# Utility_Module.net
KiCad netlist of a schematic drawn in EAGLE
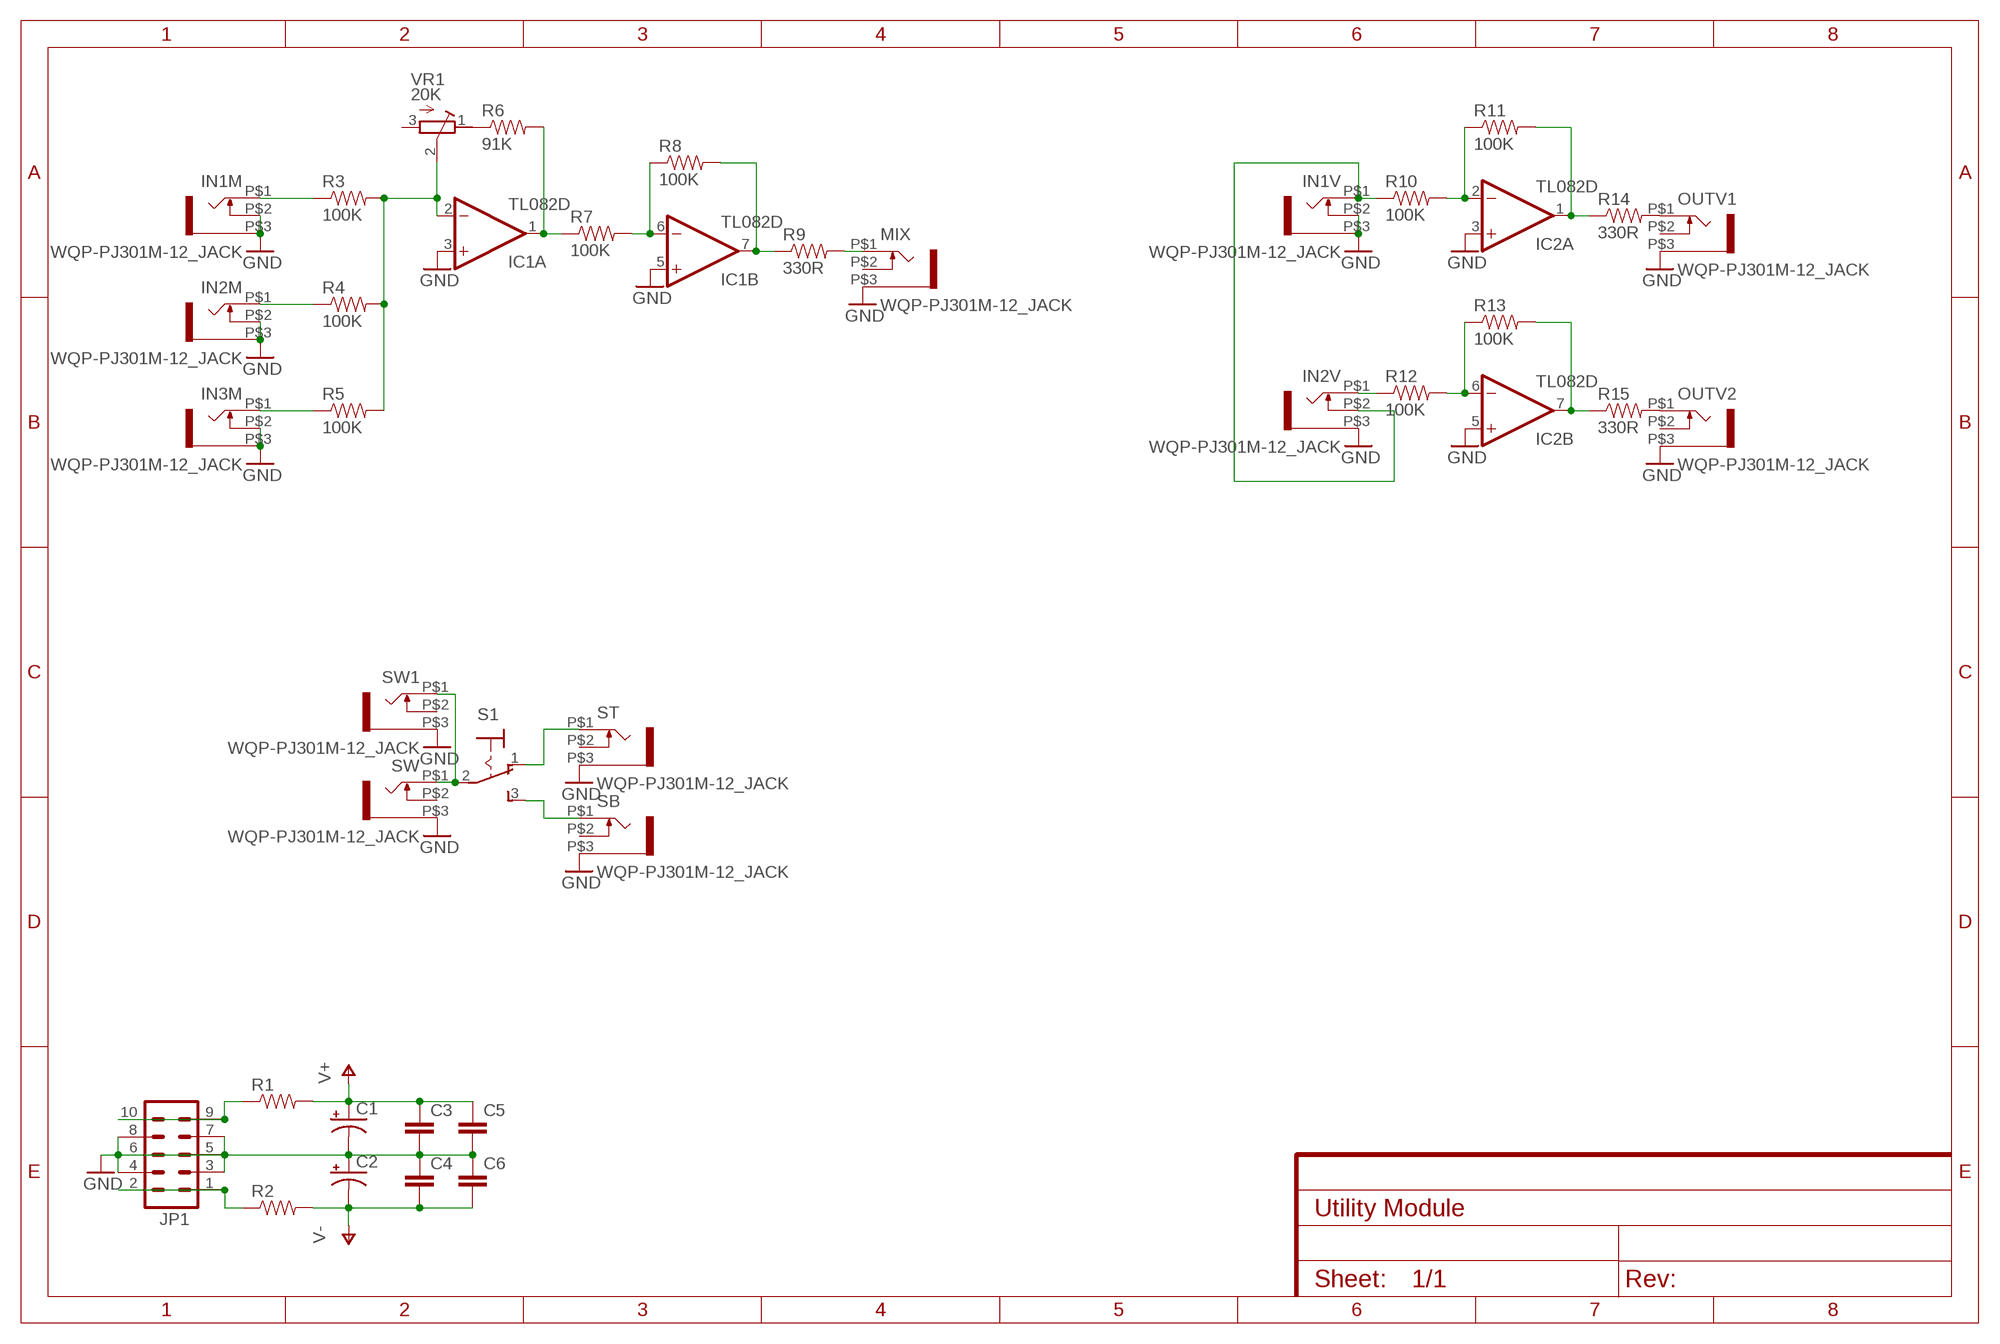
[diagram p0: schematic, sheet 1]

(export (version "E")
  (design (tool "Eeschema 10.0.6"))
  (components
    (comp (ref "C1")
      (value "CAP_POLC")
      (footprint "eagle-import:PANASONIC_C")
      (libsource (lib "eagle-import") (part "CAP_POLC"))
    )
    (comp (ref "C2")
      (value "CAP_POLC")
      (footprint "eagle-import:PANASONIC_C")
      (libsource (lib "eagle-import") (part "CAP_POLC"))
    )
    (comp (ref "C3")
      (value "CAP0805")
      (footprint "eagle-import:0805")
      (libsource (lib "eagle-import") (part "CAP0805"))
    )
    (comp (ref "C4")
      (value "CAP0805")
      (footprint "eagle-import:0805")
      (libsource (lib "eagle-import") (part "CAP0805"))
    )
    (comp (ref "C5")
      (value "CAP0805")
      (footprint "eagle-import:0805")
      (libsource (lib "eagle-import") (part "CAP0805"))
    )
    (comp (ref "C6")
      (value "CAP0805")
      (footprint "eagle-import:0805")
      (libsource (lib "eagle-import") (part "CAP0805"))
    )
    (comp (ref "IC1")
      (value "TL082D")
      (footprint "eagle-import:SO08")
      (libsource (lib "eagle-import") (part "TL082D"))
    )
    (comp (ref "IC2")
      (value "TL082D")
      (footprint "eagle-import:SO08")
      (libsource (lib "eagle-import") (part "TL082D"))
    )
    (comp (ref "IN1M")
      (value "WQP-PJ301M-12_JACK")
      (footprint "eagle-import:WQP-PJ301M-12_JACK")
      (libsource (lib "eagle-import") (part "WQP-PJ301M-12_JACK"))
    )
    (comp (ref "IN1V")
      (value "WQP-PJ301M-12_JACK")
      (footprint "eagle-import:WQP-PJ301M-12_JACK")
      (libsource (lib "eagle-import") (part "WQP-PJ301M-12_JACK"))
    )
    (comp (ref "IN2M")
      (value "WQP-PJ301M-12_JACK")
      (footprint "eagle-import:WQP-PJ301M-12_JACK")
      (libsource (lib "eagle-import") (part "WQP-PJ301M-12_JACK"))
    )
    (comp (ref "IN2V")
      (value "WQP-PJ301M-12_JACK")
      (footprint "eagle-import:WQP-PJ301M-12_JACK")
      (libsource (lib "eagle-import") (part "WQP-PJ301M-12_JACK"))
    )
    (comp (ref "IN3M")
      (value "WQP-PJ301M-12_JACK")
      (footprint "eagle-import:WQP-PJ301M-12_JACK")
      (libsource (lib "eagle-import") (part "WQP-PJ301M-12_JACK"))
    )
    (comp (ref "JP1")
      (value "M05X2PTH")
      (footprint "eagle-import:AVR_ICSP")
      (libsource (lib "eagle-import") (part "M05X2PTH"))
    )
    (comp (ref "MIX")
      (value "WQP-PJ301M-12_JACK")
      (footprint "eagle-import:WQP-PJ301M-12_JACK")
      (libsource (lib "eagle-import") (part "WQP-PJ301M-12_JACK"))
    )
    (comp (ref "OUTV1")
      (value "WQP-PJ301M-12_JACK")
      (footprint "eagle-import:WQP-PJ301M-12_JACK")
      (libsource (lib "eagle-import") (part "WQP-PJ301M-12_JACK"))
    )
    (comp (ref "OUTV2")
      (value "WQP-PJ301M-12_JACK")
      (footprint "eagle-import:WQP-PJ301M-12_JACK")
      (libsource (lib "eagle-import") (part "WQP-PJ301M-12_JACK"))
    )
    (comp (ref "R1")
      (value "RESISTOR0805-RES")
      (footprint "eagle-import:0805")
      (libsource (lib "eagle-import") (part "RESISTOR0805-RES"))
    )
    (comp (ref "R2")
      (value "RESISTOR0805-RES")
      (footprint "eagle-import:0805")
      (libsource (lib "eagle-import") (part "RESISTOR0805-RES"))
    )
    (comp (ref "R3")
      (value "100K")
      (footprint "eagle-import:0805")
      (libsource (lib "eagle-import") (part "RESISTOR0805-RES"))
    )
    (comp (ref "R4")
      (value "100K")
      (footprint "eagle-import:0805")
      (libsource (lib "eagle-import") (part "RESISTOR0805-RES"))
    )
    (comp (ref "R5")
      (value "100K")
      (footprint "eagle-import:0805")
      (libsource (lib "eagle-import") (part "RESISTOR0805-RES"))
    )
    (comp (ref "R6")
      (value "91K")
      (footprint "eagle-import:0805")
      (libsource (lib "eagle-import") (part "RESISTOR0805-RES"))
    )
    (comp (ref "R7")
      (value "100K")
      (footprint "eagle-import:0805")
      (libsource (lib "eagle-import") (part "RESISTOR0805-RES"))
    )
    (comp (ref "R8")
      (value "100K")
      (footprint "eagle-import:0805")
      (libsource (lib "eagle-import") (part "RESISTOR0805-RES"))
    )
    (comp (ref "R9")
      (value "330R")
      (footprint "eagle-import:0805")
      (libsource (lib "eagle-import") (part "RESISTOR0805-RES"))
    )
    (comp (ref "R10")
      (value "100K")
      (footprint "eagle-import:0805")
      (libsource (lib "eagle-import") (part "RESISTOR0805-RES"))
    )
    (comp (ref "R11")
      (value "100K")
      (footprint "eagle-import:0805")
      (libsource (lib "eagle-import") (part "RESISTOR0805-RES"))
    )
    (comp (ref "R12")
      (value "100K")
      (footprint "eagle-import:0805")
      (libsource (lib "eagle-import") (part "RESISTOR0805-RES"))
    )
    (comp (ref "R13")
      (value "100K")
      (footprint "eagle-import:0805")
      (libsource (lib "eagle-import") (part "RESISTOR0805-RES"))
    )
    (comp (ref "R14")
      (value "330R")
      (footprint "eagle-import:0805")
      (libsource (lib "eagle-import") (part "RESISTOR0805-RES"))
    )
    (comp (ref "R15")
      (value "330R")
      (footprint "eagle-import:0805")
      (libsource (lib "eagle-import") (part "RESISTOR0805-RES"))
    )
    (comp (ref "S1")
      (value "M9040P")
      (footprint "eagle-import:M9040P")
      (libsource (lib "eagle-import") (part "M9040P"))
    )
    (comp (ref "SB")
      (value "WQP-PJ301M-12_JACK")
      (footprint "eagle-import:WQP-PJ301M-12_JACK")
      (libsource (lib "eagle-import") (part "WQP-PJ301M-12_JACK"))
    )
    (comp (ref "ST")
      (value "WQP-PJ301M-12_JACK")
      (footprint "eagle-import:WQP-PJ301M-12_JACK")
      (libsource (lib "eagle-import") (part "WQP-PJ301M-12_JACK"))
    )
    (comp (ref "SW")
      (value "WQP-PJ301M-12_JACK")
      (footprint "eagle-import:WQP-PJ301M-12_JACK")
      (libsource (lib "eagle-import") (part "WQP-PJ301M-12_JACK"))
    )
    (comp (ref "SW1")
      (value "WQP-PJ301M-12_JACK")
      (footprint "eagle-import:WQP-PJ301M-12_JACK")
      (libsource (lib "eagle-import") (part "WQP-PJ301M-12_JACK"))
    )
    (comp (ref "VR1")
      (value "20K")
      (footprint "eagle-import:RTRIM3314G")
      (libsource (lib "eagle-import") (part "R-TRIMM3314G"))
    )
  )
  (nets
    (net (code "1") (name "GND") (class "Default")
      (node (ref "C1") (pin "-") (pinfunction "-_-") (pintype "passive"))
      (node (ref "C2") (pin "+") (pinfunction "+_+") (pintype "passive"))
      (node (ref "C3") (pin "2") (pinfunction "2_2") (pintype "passive"))
      (node (ref "C4") (pin "1") (pinfunction "1_1") (pintype "passive"))
      (node (ref "C5") (pin "2") (pinfunction "2_2") (pintype "passive"))
      (node (ref "C6") (pin "1") (pinfunction "1_1") (pintype "passive"))
      (node (ref "IC1") (pin "3") (pinfunction "+IN_3") (pintype "input"))
      (node (ref "IC1") (pin "5") (pinfunction "+IN_5") (pintype "input"))
      (node (ref "IC2") (pin "3") (pinfunction "+IN_3") (pintype "input"))
      (node (ref "IC2") (pin "5") (pinfunction "+IN_5") (pintype "input"))
      (node (ref "IN1M") (pin "P$2") (pinfunction "3_P$2") (pintype "passive"))
      (node (ref "IN1M") (pin "P$3") (pinfunction "1_P$3") (pintype "passive"))
      (node (ref "IN1V") (pin "P$2") (pinfunction "3_P$2") (pintype "passive"))
      (node (ref "IN1V") (pin "P$3") (pinfunction "1_P$3") (pintype "passive"))
      (node (ref "IN2M") (pin "P$2") (pinfunction "3_P$2") (pintype "passive"))
      (node (ref "IN2M") (pin "P$3") (pinfunction "1_P$3") (pintype "passive"))
      (node (ref "IN2V") (pin "P$3") (pinfunction "1_P$3") (pintype "passive"))
      (node (ref "IN3M") (pin "P$2") (pinfunction "3_P$2") (pintype "passive"))
      (node (ref "IN3M") (pin "P$3") (pinfunction "1_P$3") (pintype "passive"))
      (node (ref "JP1") (pin "3") (pinfunction "3_3") (pintype "passive"))
      (node (ref "JP1") (pin "4") (pinfunction "4_4") (pintype "passive"))
      (node (ref "JP1") (pin "5") (pinfunction "5_5") (pintype "passive"))
      (node (ref "JP1") (pin "6") (pinfunction "6_6") (pintype "passive"))
      (node (ref "JP1") (pin "7") (pinfunction "7_7") (pintype "passive"))
      (node (ref "JP1") (pin "8") (pinfunction "8_8") (pintype "passive"))
      (node (ref "MIX") (pin "P$3") (pinfunction "1_P$3") (pintype "passive"))
      (node (ref "OUTV1") (pin "P$3") (pinfunction "1_P$3") (pintype "passive"))
      (node (ref "OUTV2") (pin "P$3") (pinfunction "1_P$3") (pintype "passive"))
      (node (ref "SB") (pin "P$3") (pinfunction "1_P$3") (pintype "passive"))
      (node (ref "ST") (pin "P$3") (pinfunction "1_P$3") (pintype "passive"))
      (node (ref "SW") (pin "P$3") (pinfunction "1_P$3") (pintype "passive"))
      (node (ref "SW1") (pin "P$3") (pinfunction "1_P$3") (pintype "passive"))
    )
    (net (code "2") (name "Net-(IC1A--IN)") (class "Default")
      (node (ref "IC1") (pin "2") (pinfunction "-IN_2") (pintype "input"))
      (node (ref "R3") (pin "2") (pinfunction "2_2") (pintype "passive"))
      (node (ref "R4") (pin "2") (pinfunction "2_2") (pintype "passive"))
      (node (ref "R5") (pin "2") (pinfunction "2_2") (pintype "passive"))
      (node (ref "VR1") (pin "2") (pinfunction "S_2") (pintype "passive"))
    )
    (net (code "3") (name "Net-(IC1A-OUT)") (class "Default")
      (node (ref "IC1") (pin "1") (pinfunction "OUT_1") (pintype "output"))
      (node (ref "R6") (pin "2") (pinfunction "2_2") (pintype "passive"))
      (node (ref "R7") (pin "1") (pinfunction "1_1") (pintype "passive"))
    )
    (net (code "4") (name "Net-(IC1B--IN)") (class "Default")
      (node (ref "IC1") (pin "6") (pinfunction "-IN_6") (pintype "input"))
      (node (ref "R7") (pin "2") (pinfunction "2_2") (pintype "passive"))
      (node (ref "R8") (pin "1") (pinfunction "1_1") (pintype "passive"))
    )
    (net (code "5") (name "Net-(IC1B-OUT)") (class "Default")
      (node (ref "IC1") (pin "7") (pinfunction "OUT_7") (pintype "output"))
      (node (ref "R8") (pin "2") (pinfunction "2_2") (pintype "passive"))
      (node (ref "R9") (pin "1") (pinfunction "1_1") (pintype "passive"))
    )
    (net (code "6") (name "Net-(IC2A--IN)") (class "Default")
      (node (ref "IC2") (pin "2") (pinfunction "-IN_2") (pintype "input"))
      (node (ref "R10") (pin "2") (pinfunction "2_2") (pintype "passive"))
      (node (ref "R11") (pin "1") (pinfunction "1_1") (pintype "passive"))
    )
    (net (code "7") (name "Net-(IC2A-OUT)") (class "Default")
      (node (ref "IC2") (pin "1") (pinfunction "OUT_1") (pintype "output"))
      (node (ref "R11") (pin "2") (pinfunction "2_2") (pintype "passive"))
      (node (ref "R14") (pin "1") (pinfunction "1_1") (pintype "passive"))
    )
    (net (code "8") (name "Net-(IC2B--IN)") (class "Default")
      (node (ref "IC2") (pin "6") (pinfunction "-IN_6") (pintype "input"))
      (node (ref "R12") (pin "2") (pinfunction "2_2") (pintype "passive"))
      (node (ref "R13") (pin "1") (pinfunction "1_1") (pintype "passive"))
    )
    (net (code "9") (name "Net-(IC2B-OUT)") (class "Default")
      (node (ref "IC2") (pin "7") (pinfunction "OUT_7") (pintype "output"))
      (node (ref "R13") (pin "2") (pinfunction "2_2") (pintype "passive"))
      (node (ref "R15") (pin "1") (pinfunction "1_1") (pintype "passive"))
    )
    (net (code "10") (name "Net-(IN1M-2)") (class "Default")
      (node (ref "IN1M") (pin "P$1") (pinfunction "2_P$1") (pintype "passive"))
      (node (ref "R3") (pin "1") (pinfunction "1_1") (pintype "passive"))
    )
    (net (code "11") (name "Net-(IN1V-2)") (class "Default")
      (node (ref "IN1V") (pin "P$1") (pinfunction "2_P$1") (pintype "passive"))
      (node (ref "IN2V") (pin "P$2") (pinfunction "3_P$2") (pintype "passive"))
      (node (ref "R10") (pin "1") (pinfunction "1_1") (pintype "passive"))
    )
    (net (code "12") (name "Net-(IN2M-2)") (class "Default")
      (node (ref "IN2M") (pin "P$1") (pinfunction "2_P$1") (pintype "passive"))
      (node (ref "R4") (pin "1") (pinfunction "1_1") (pintype "passive"))
    )
    (net (code "13") (name "Net-(IN2V-2)") (class "Default")
      (node (ref "IN2V") (pin "P$1") (pinfunction "2_P$1") (pintype "passive"))
      (node (ref "R12") (pin "1") (pinfunction "1_1") (pintype "passive"))
    )
    (net (code "14") (name "Net-(IN3M-2)") (class "Default")
      (node (ref "IN3M") (pin "P$1") (pinfunction "2_P$1") (pintype "passive"))
      (node (ref "R5") (pin "1") (pinfunction "1_1") (pintype "passive"))
    )
    (net (code "15") (name "Net-(JP1-Pad1)") (class "Default")
      (node (ref "JP1") (pin "1") (pinfunction "1_1") (pintype "passive"))
      (node (ref "JP1") (pin "2") (pinfunction "2_2") (pintype "passive"))
      (node (ref "R2") (pin "1") (pinfunction "1_1") (pintype "passive"))
    )
    (net (code "16") (name "Net-(JP1-Pad10)") (class "Default")
      (node (ref "JP1") (pin "10") (pinfunction "10_10") (pintype "passive"))
      (node (ref "JP1") (pin "9") (pinfunction "9_9") (pintype "passive"))
      (node (ref "R1") (pin "1") (pinfunction "1_1") (pintype "passive"))
    )
    (net (code "17") (name "Net-(MIX-2)") (class "Default")
      (node (ref "MIX") (pin "P$1") (pinfunction "2_P$1") (pintype "passive"))
      (node (ref "R9") (pin "2") (pinfunction "2_2") (pintype "passive"))
    )
    (net (code "18") (name "Net-(OUTV1-2)") (class "Default")
      (node (ref "OUTV1") (pin "P$1") (pinfunction "2_P$1") (pintype "passive"))
      (node (ref "R14") (pin "2") (pinfunction "2_2") (pintype "passive"))
    )
    (net (code "19") (name "Net-(OUTV2-2)") (class "Default")
      (node (ref "OUTV2") (pin "P$1") (pinfunction "2_P$1") (pintype "passive"))
      (node (ref "R15") (pin "2") (pinfunction "2_2") (pintype "passive"))
    )
    (net (code "20") (name "Net-(S1-O)") (class "Default")
      (node (ref "S1") (pin "1") (pinfunction "O_1") (pintype "passive"))
      (node (ref "ST") (pin "P$1") (pinfunction "2_P$1") (pintype "passive"))
    )
    (net (code "21") (name "Net-(S1-P)") (class "Default")
      (node (ref "S1") (pin "2") (pinfunction "P_2") (pintype "passive"))
      (node (ref "SW") (pin "P$1") (pinfunction "2_P$1") (pintype "passive"))
      (node (ref "SW1") (pin "P$1") (pinfunction "2_P$1") (pintype "passive"))
    )
    (net (code "22") (name "Net-(S1-S)") (class "Default")
      (node (ref "S1") (pin "3") (pinfunction "S_3") (pintype "passive"))
      (node (ref "SB") (pin "P$1") (pinfunction "2_P$1") (pintype "passive"))
    )
    (net (code "23") (name "Net-(VR1-E)") (class "Default")
      (node (ref "R6") (pin "1") (pinfunction "1_1") (pintype "passive"))
      (node (ref "VR1") (pin "1") (pinfunction "E_1") (pintype "passive"))
    )
    (net (code "24") (name "V+") (class "Default")
      (node (ref "C1") (pin "+") (pinfunction "+_+") (pintype "passive"))
      (node (ref "C3") (pin "1") (pinfunction "1_1") (pintype "passive"))
      (node (ref "C5") (pin "1") (pinfunction "1_1") (pintype "passive"))
      (node (ref "R1") (pin "2") (pinfunction "2_2") (pintype "passive"))
    )
    (net (code "25") (name "V-") (class "Default")
      (node (ref "C2") (pin "-") (pinfunction "-_-") (pintype "passive"))
      (node (ref "C4") (pin "2") (pinfunction "2_2") (pintype "passive"))
      (node (ref "C6") (pin "2") (pinfunction "2_2") (pintype "passive"))
      (node (ref "R2") (pin "2") (pinfunction "2_2") (pintype "passive"))
    )
    (net (code "26") (name "unconnected-(MIX-3-PadP$2)") (class "Default")
      (node (ref "MIX") (pin "P$2") (pinfunction "3_P$2") (pintype "passive"))
    )
    (net (code "27") (name "unconnected-(OUTV1-3-PadP$2)") (class "Default")
      (node (ref "OUTV1") (pin "P$2") (pinfunction "3_P$2") (pintype "passive"))
    )
    (net (code "28") (name "unconnected-(OUTV2-3-PadP$2)") (class "Default")
      (node (ref "OUTV2") (pin "P$2") (pinfunction "3_P$2") (pintype "passive"))
    )
    (net (code "29") (name "unconnected-(SB-3-PadP$2)") (class "Default")
      (node (ref "SB") (pin "P$2") (pinfunction "3_P$2") (pintype "passive"))
    )
    (net (code "30") (name "unconnected-(ST-3-PadP$2)") (class "Default")
      (node (ref "ST") (pin "P$2") (pinfunction "3_P$2") (pintype "passive"))
    )
    (net (code "31") (name "unconnected-(SW-3-PadP$2)") (class "Default")
      (node (ref "SW") (pin "P$2") (pinfunction "3_P$2") (pintype "passive"))
    )
    (net (code "32") (name "unconnected-(SW1-3-PadP$2)") (class "Default")
      (node (ref "SW1") (pin "P$2") (pinfunction "3_P$2") (pintype "passive"))
    )
    (net (code "33") (name "unconnected-(VR1-A-Pad3)") (class "Default")
      (node (ref "VR1") (pin "3") (pinfunction "A_3") (pintype "passive"))
    )
  )
)
